# DM0255_MTP006.net
KiCad netlist of a schematic drawn in Altium Designer
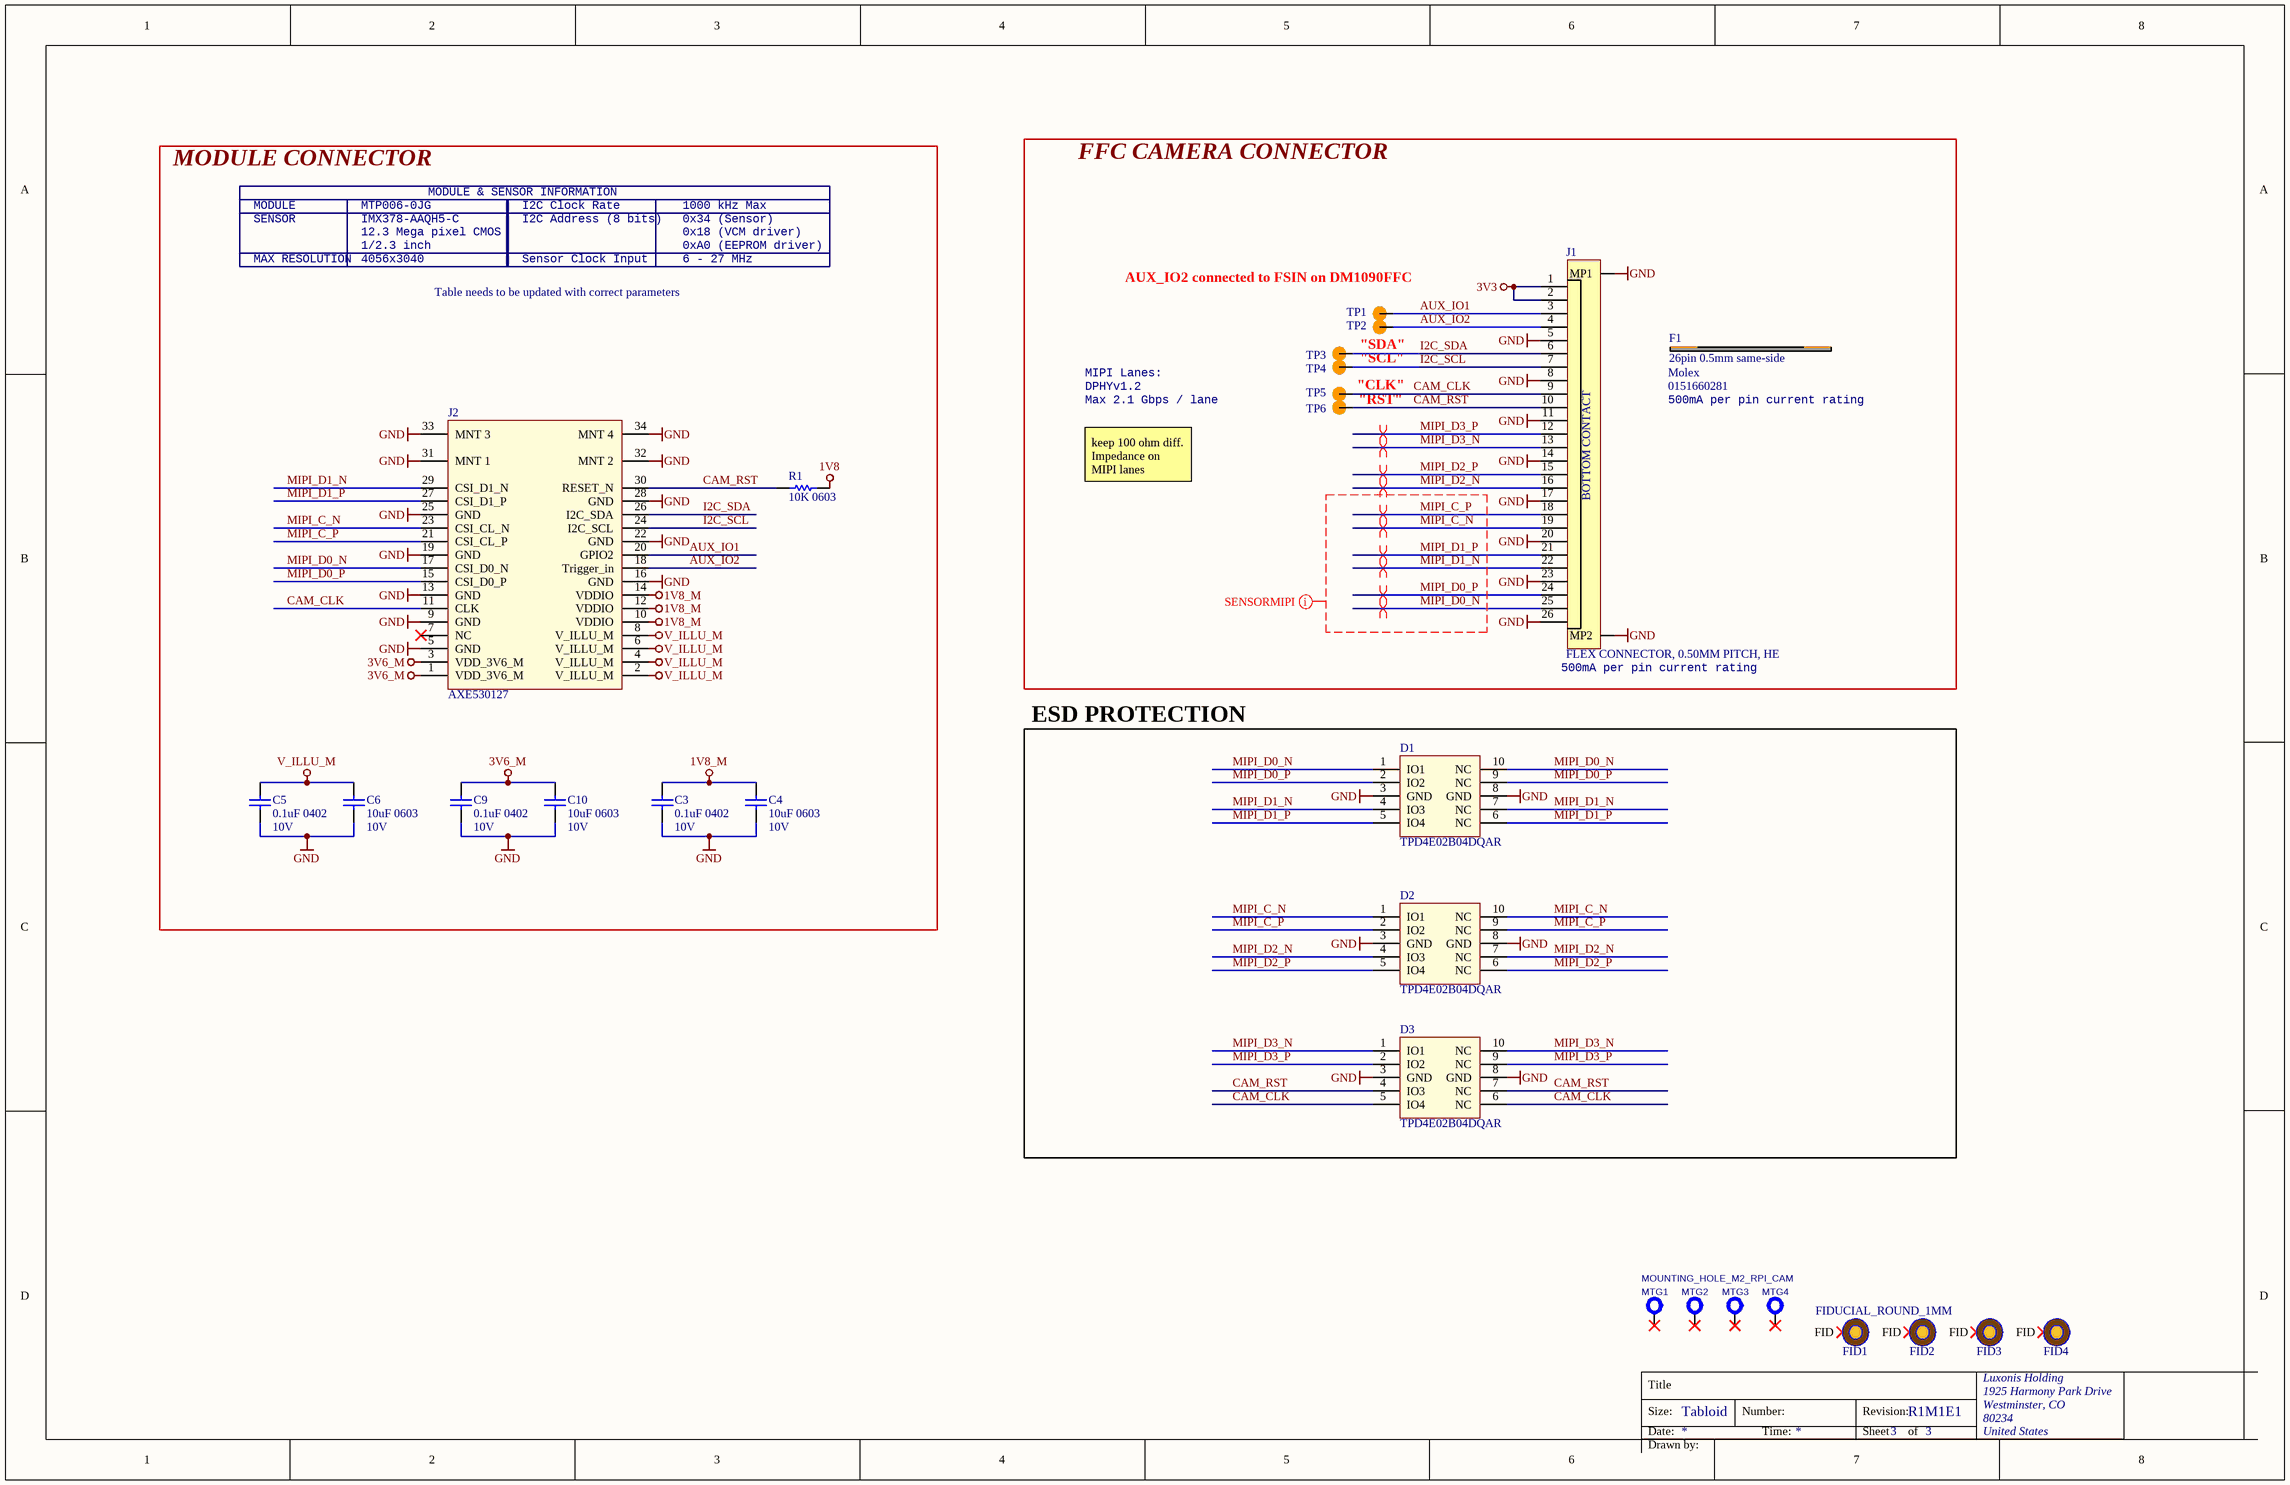
[diagram p0: DM0255_MTP006.SchDoc]

(export (version "E")
  (design (tool "Eeschema 10.0.6"))
  (components
    (comp (ref "C3")
      (value "0.1uF 0402")
      (footprint "CAP_Altium_Vault_Generic:CAPC0402(1005)70_N")
      (description "CAP CER 0.1UF 10V X7R 0402 5%")
      (fields (field (name "TOLERANCE") "5%") (field (name "VOLTAGE RATING") "10V"))
      (libsource (lib "LuxonisMaster") (part "GRM155R71A104JA01D"))
    )
    (comp (ref "C4")
      (value "10uF 0603")
      (footprint "CAP_Altium_Vault_Generic:CAPC0603(1608)100_N")
      (description "CAP CER 10UF 10V X5R 0603 20%")
      (fields (field (name "TOLERANCE") "20%") (field (name "VOLTAGE RATING") "10V"))
      (libsource (lib "LuxonisMaster") (part "GRM188R61A106ME69D"))
    )
    (comp (ref "C5")
      (value "0.1uF 0402")
      (footprint "CAP_Altium_Vault_Generic:CAPC0402(1005)70_N")
      (description "CAP CER 0.1UF 10V X7R 0402 5%")
      (fields (field (name "TOLERANCE") "5%") (field (name "VOLTAGE RATING") "10V"))
      (libsource (lib "LuxonisMaster") (part "GRM155R71A104JA01D"))
    )
    (comp (ref "C6")
      (value "10uF 0603")
      (footprint "CAP_Altium_Vault_Generic:CAPC0603(1608)100_N")
      (description "CAP CER 10UF 10V X5R 0603 20%")
      (fields (field (name "TOLERANCE") "20%") (field (name "VOLTAGE RATING") "10V"))
      (libsource (lib "LuxonisMaster") (part "GRM188R61A106ME69D"))
    )
    (comp (ref "C9")
      (value "0.1uF 0402")
      (footprint "CAP_Altium_Vault_Generic:CAPC0402(1005)70_N")
      (description "CAP CER 0.1UF 10V X7R 0402 5%")
      (fields (field (name "TOLERANCE") "5%") (field (name "VOLTAGE RATING") "10V"))
      (libsource (lib "LuxonisMaster") (part "GRM155R71A104JA01D"))
    )
    (comp (ref "C10")
      (value "10uF 0603")
      (footprint "CAP_Altium_Vault_Generic:CAPC0603(1608)100_N")
      (description "CAP CER 10UF 10V X5R 0603 20%")
      (fields (field (name "TOLERANCE") "20%") (field (name "VOLTAGE RATING") "10V"))
      (libsource (lib "LuxonisMaster") (part "GRM188R61A106ME69D"))
    )
    (comp (ref "D1")
      (value "TPD4E02B04DQAR")
      (footprint "LuxonisMaster:TPD4E02B04DQAR")
      (libsource (lib "LuxonisMaster") (part "TPD4E02B04DQAR"))
    )
    (comp (ref "D2")
      (value "TPD4E02B04DQAR")
      (footprint "LuxonisMaster:TPD4E02B04DQAR")
      (libsource (lib "LuxonisMaster") (part "TPD4E02B04DQAR"))
    )
    (comp (ref "D3")
      (value "TPD4E02B04DQAR")
      (footprint "LuxonisMaster:TPD4E02B04DQAR")
      (libsource (lib "LuxonisMaster") (part "TPD4E02B04DQAR"))
    )
    (comp (ref "F1")
      (value "26pin 0.5mm same-side")
      (description "CABLE FFC 26POS 0.50MM 6\"")
      (fields
        (field (name "MANUFACTURER 1") "Molex")
        (field (name "MANUFACTURER PART NUMBER 1") "0151660281")
      )
      (libsource (lib "BG0249_R1M1E1") (part "0151660281"))
    )
    (comp (ref "FID1")
      (value "FIDUCIAL_ROUND_1MM")
      (footprint "LuxonisMaster:FIDUCIAL_ROUND_1MM")
      (description "Fiducial with various available footprints")
      (libsource (lib "LuxonisMaster") (part "FIDUCIAL"))
    )
    (comp (ref "FID2")
      (value "FIDUCIAL_ROUND_1MM")
      (footprint "LuxonisMaster:FIDUCIAL_ROUND_1MM")
      (description "Fiducial with various available footprints")
      (libsource (lib "LuxonisMaster") (part "FIDUCIAL"))
    )
    (comp (ref "FID3")
      (value "FIDUCIAL_ROUND_1MM")
      (footprint "LuxonisMaster:FIDUCIAL_ROUND_1MM")
      (description "Fiducial with various available footprints")
      (libsource (lib "LuxonisMaster") (part "FIDUCIAL"))
    )
    (comp (ref "FID4")
      (value "FIDUCIAL_ROUND_1MM")
      (footprint "LuxonisMaster:FIDUCIAL_ROUND_1MM")
      (description "Fiducial with various available footprints")
      (libsource (lib "LuxonisMaster") (part "FIDUCIAL"))
    )
    (comp (ref "J1")
      (value "FLEX CONNECTOR, 0.50MM PITCH, HE")
      (footprint "F32R-1A7H1-11026")
      (description "26 Position FFC, FPC Connector Contacts, Bottom 0.020\" (0.50mm) Surface Mount, Right Angle")
      (libsource (lib "DM0255") (part "F32R-1A7H1-11026"))
    )
    (comp (ref "J2")
      (value "AXE530127")
      (footprint "AXE530127")
      (description "Narrow Pitch Connector (Board to FPC) 0.4mm")
      (libsource (lib "DM0255") (part "AXE530127"))
    )
    (comp (ref "MTG1")
      (value "MOUNTING_HOLE_M2_RPI_CAM")
      (footprint "LuxonisMaster:MOUNTING_HOLE_M2_RPI_CAM")
      (description "=CurrentFootprint")
      (libsource (lib "LuxonisMaster") (part "MP_Mounting-Holes"))
    )
    (comp (ref "MTG2")
      (value "MOUNTING_HOLE_M2_RPI_CAM")
      (footprint "LuxonisMaster:MOUNTING_HOLE_M2_RPI_CAM")
      (description "=CurrentFootprint")
      (libsource (lib "LuxonisMaster") (part "MP_Mounting-Holes"))
    )
    (comp (ref "MTG3")
      (value "MOUNTING_HOLE_M2_RPI_CAM")
      (footprint "LuxonisMaster:MOUNTING_HOLE_M2_RPI_CAM")
      (description "=CurrentFootprint")
      (libsource (lib "LuxonisMaster") (part "MP_Mounting-Holes"))
    )
    (comp (ref "MTG4")
      (value "MOUNTING_HOLE_M2_RPI_CAM")
      (footprint "LuxonisMaster:MOUNTING_HOLE_M2_RPI_CAM")
      (description "=CurrentFootprint")
      (libsource (lib "LuxonisMaster") (part "MP_Mounting-Holes"))
    )
    (comp (ref "R1")
      (value "10K 0603")
      (footprint "RES_Altium_Vault_Generic:RESC0603(1608)_N")
      (description "RES SMD 10K OHM 1% 1/10W 0603")
      (fields (field (name "TOLERANCE") "1%"))
      (libsource (lib "LuxonisMaster") (part "RC0603FR-0710KL"))
    )
    (comp (ref "TP1")
      (value "TP100_200_NS")
      (footprint "LuxonisMaster:TP100_200_NS")
      (libsource (lib "LuxonisMaster") (part "TEST_POINT"))
    )
    (comp (ref "TP2")
      (value "TP100_200_NS")
      (footprint "LuxonisMaster:TP100_200_NS")
      (libsource (lib "LuxonisMaster") (part "TEST_POINT"))
    )
    (comp (ref "TP3")
      (value "TP100_200_NS")
      (footprint "LuxonisMaster:TP100_200_NS")
      (libsource (lib "LuxonisMaster") (part "TEST_POINT"))
    )
    (comp (ref "TP4")
      (value "TP100_200_NS")
      (footprint "LuxonisMaster:TP100_200_NS")
      (libsource (lib "LuxonisMaster") (part "TEST_POINT"))
    )
    (comp (ref "TP5")
      (value "TP100_200_NS")
      (footprint "LuxonisMaster:TP100_200_NS")
      (libsource (lib "LuxonisMaster") (part "TEST_POINT"))
    )
    (comp (ref "TP6")
      (value "TP100_200_NS")
      (footprint "LuxonisMaster:TP100_200_NS")
      (libsource (lib "LuxonisMaster") (part "TEST_POINT"))
    )
  )
  (nets
    (net (code "1") (name "/AUX_IO1") (class "Default")
      (node (ref "J1") (pin "3") (pinfunction "3_3") (pintype "passive"))
      (node (ref "J2") (pin "20") (pinfunction "GPIO2_20") (pintype "passive"))
      (node (ref "TP1") (pin "1") (pintype "passive"))
    )
    (net (code "2") (name "/AUX_IO2") (class "Default")
      (node (ref "J1") (pin "4") (pinfunction "4_4") (pintype "passive"))
      (node (ref "J2") (pin "18") (pinfunction "Trigger_in_18") (pintype "passive"))
      (node (ref "TP2") (pin "1") (pintype "passive"))
    )
    (net (code "3") (name "/CAM_CLK") (class "Default")
      (node (ref "D3") (pin "5") (pinfunction "IO4_5") (pintype "passive"))
      (node (ref "D3") (pin "6") (pinfunction "NC_6") (pintype "passive"))
      (node (ref "J1") (pin "9") (pinfunction "9_9") (pintype "passive"))
      (node (ref "J2") (pin "11") (pinfunction "CLK_11") (pintype "passive"))
      (node (ref "TP5") (pin "1") (pintype "passive"))
    )
    (net (code "4") (name "/CAM_RST") (class "Default")
      (node (ref "D3") (pin "4") (pinfunction "IO3_4") (pintype "passive"))
      (node (ref "D3") (pin "7") (pinfunction "NC_7") (pintype "passive"))
      (node (ref "J1") (pin "10") (pinfunction "10_10") (pintype "passive"))
      (node (ref "J2") (pin "30") (pinfunction "RESET_N_30") (pintype "passive"))
      (node (ref "R1") (pin "1") (pinfunction "1_1") (pintype "passive"))
      (node (ref "TP6") (pin "1") (pintype "passive"))
    )
    (net (code "5") (name "/I2C_SCL") (class "Default")
      (node (ref "J1") (pin "7") (pinfunction "7_7") (pintype "passive"))
      (node (ref "J2") (pin "24") (pinfunction "I2C_SCL_24") (pintype "passive"))
      (node (ref "TP4") (pin "1") (pintype "passive"))
    )
    (net (code "6") (name "/I2C_SDA") (class "Default")
      (node (ref "J1") (pin "6") (pinfunction "6_6") (pintype "passive"))
      (node (ref "J2") (pin "26") (pinfunction "I2C_SDA_26") (pintype "passive"))
      (node (ref "TP3") (pin "1") (pintype "passive"))
    )
    (net (code "7") (name "/MIPI_C_N") (class "Default")
      (node (ref "D2") (pin "1") (pinfunction "IO1_1") (pintype "passive"))
      (node (ref "D2") (pin "10") (pinfunction "NC_10") (pintype "passive"))
      (node (ref "J1") (pin "19") (pinfunction "19_19") (pintype "passive"))
      (node (ref "J2") (pin "23") (pinfunction "CSI_CL_N_23") (pintype "passive"))
    )
    (net (code "8") (name "/MIPI_C_P") (class "Default")
      (node (ref "D2") (pin "2") (pinfunction "IO2_2") (pintype "passive"))
      (node (ref "D2") (pin "9") (pinfunction "NC_9") (pintype "passive"))
      (node (ref "J1") (pin "18") (pinfunction "18_18") (pintype "passive"))
      (node (ref "J2") (pin "21") (pinfunction "CSI_CL_P_21") (pintype "passive"))
    )
    (net (code "9") (name "/MIPI_D0_N") (class "Default")
      (node (ref "D1") (pin "1") (pinfunction "IO1_1") (pintype "passive"))
      (node (ref "D1") (pin "10") (pinfunction "NC_10") (pintype "passive"))
      (node (ref "J1") (pin "25") (pinfunction "25_25") (pintype "passive"))
      (node (ref "J2") (pin "17") (pinfunction "CSI_D0_N_17") (pintype "passive"))
    )
    (net (code "10") (name "/MIPI_D0_P") (class "Default")
      (node (ref "D1") (pin "2") (pinfunction "IO2_2") (pintype "passive"))
      (node (ref "D1") (pin "9") (pinfunction "NC_9") (pintype "passive"))
      (node (ref "J1") (pin "24") (pinfunction "24_24") (pintype "passive"))
      (node (ref "J2") (pin "15") (pinfunction "CSI_D0_P_15") (pintype "passive"))
    )
    (net (code "11") (name "/MIPI_D1_N") (class "Default")
      (node (ref "D1") (pin "4") (pinfunction "IO3_4") (pintype "passive"))
      (node (ref "D1") (pin "7") (pinfunction "NC_7") (pintype "passive"))
      (node (ref "J1") (pin "22") (pinfunction "22_22") (pintype "passive"))
      (node (ref "J2") (pin "29") (pinfunction "CSI_D1_N_29") (pintype "passive"))
    )
    (net (code "12") (name "/MIPI_D1_P") (class "Default")
      (node (ref "D1") (pin "5") (pinfunction "IO4_5") (pintype "passive"))
      (node (ref "D1") (pin "6") (pinfunction "NC_6") (pintype "passive"))
      (node (ref "J1") (pin "21") (pinfunction "21_21") (pintype "passive"))
      (node (ref "J2") (pin "27") (pinfunction "CSI_D1_P_27") (pintype "passive"))
    )
    (net (code "13") (name "/MIPI_D2_N") (class "Default")
      (node (ref "D2") (pin "4") (pinfunction "IO3_4") (pintype "passive"))
      (node (ref "D2") (pin "7") (pinfunction "NC_7") (pintype "passive"))
      (node (ref "J1") (pin "16") (pinfunction "16_16") (pintype "passive"))
    )
    (net (code "14") (name "/MIPI_D2_P") (class "Default")
      (node (ref "D2") (pin "5") (pinfunction "IO4_5") (pintype "passive"))
      (node (ref "D2") (pin "6") (pinfunction "NC_6") (pintype "passive"))
      (node (ref "J1") (pin "15") (pinfunction "15_15") (pintype "passive"))
    )
    (net (code "15") (name "/MIPI_D3_N") (class "Default")
      (node (ref "D3") (pin "1") (pinfunction "IO1_1") (pintype "passive"))
      (node (ref "D3") (pin "10") (pinfunction "NC_10") (pintype "passive"))
      (node (ref "J1") (pin "13") (pinfunction "13_13") (pintype "passive"))
    )
    (net (code "16") (name "/MIPI_D3_P") (class "Default")
      (node (ref "D3") (pin "2") (pinfunction "IO2_2") (pintype "passive"))
      (node (ref "D3") (pin "9") (pinfunction "NC_9") (pintype "passive"))
      (node (ref "J1") (pin "12") (pinfunction "12_12") (pintype "passive"))
    )
    (net (code "17") (name "1V8") (class "Default")
      (node (ref "R1") (pin "2") (pinfunction "2_2") (pintype "passive"))
    )
    (net (code "18") (name "1V8_M") (class "Default")
      (node (ref "C3") (pin "2") (pinfunction "2_2") (pintype "passive"))
      (node (ref "C4") (pin "2") (pinfunction "2_2") (pintype "passive"))
      (node (ref "J2") (pin "10") (pinfunction "VDDIO_10") (pintype "passive"))
      (node (ref "J2") (pin "12") (pinfunction "VDDIO_12") (pintype "passive"))
      (node (ref "J2") (pin "14") (pinfunction "VDDIO_14") (pintype "passive"))
    )
    (net (code "19") (name "3V3") (class "Default")
      (node (ref "J1") (pin "1") (pinfunction "1_1") (pintype "passive"))
      (node (ref "J1") (pin "2") (pinfunction "2_2") (pintype "passive"))
    )
    (net (code "20") (name "3V6_M") (class "Default")
      (node (ref "C10") (pin "2") (pinfunction "2_2") (pintype "passive"))
      (node (ref "C9") (pin "2") (pinfunction "2_2") (pintype "passive"))
      (node (ref "J2") (pin "1") (pinfunction "VDD_3V6_M_1") (pintype "passive"))
      (node (ref "J2") (pin "3") (pinfunction "VDD_3V6_M_3") (pintype "passive"))
    )
    (net (code "21") (name "GND") (class "Default")
      (node (ref "C10") (pin "1") (pinfunction "1_1") (pintype "passive"))
      (node (ref "C3") (pin "1") (pinfunction "1_1") (pintype "passive"))
      (node (ref "C4") (pin "1") (pinfunction "1_1") (pintype "passive"))
      (node (ref "C5") (pin "1") (pinfunction "1_1") (pintype "passive"))
      (node (ref "C6") (pin "1") (pinfunction "1_1") (pintype "passive"))
      (node (ref "C9") (pin "1") (pinfunction "1_1") (pintype "passive"))
      (node (ref "D1") (pin "3") (pinfunction "GND_3") (pintype "passive"))
      (node (ref "D1") (pin "8") (pinfunction "GND_8") (pintype "passive"))
      (node (ref "D2") (pin "3") (pinfunction "GND_3") (pintype "passive"))
      (node (ref "D2") (pin "8") (pinfunction "GND_8") (pintype "passive"))
      (node (ref "D3") (pin "3") (pinfunction "GND_3") (pintype "passive"))
      (node (ref "D3") (pin "8") (pinfunction "GND_8") (pintype "passive"))
      (node (ref "J1") (pin "11") (pinfunction "11_11") (pintype "passive"))
      (node (ref "J1") (pin "14") (pinfunction "14_14") (pintype "passive"))
      (node (ref "J1") (pin "17") (pinfunction "17_17") (pintype "passive"))
      (node (ref "J1") (pin "20") (pinfunction "20_20") (pintype "passive"))
      (node (ref "J1") (pin "23") (pinfunction "23_23") (pintype "passive"))
      (node (ref "J1") (pin "26") (pinfunction "26_26") (pintype "passive"))
      (node (ref "J1") (pin "5") (pinfunction "5_5") (pintype "passive"))
      (node (ref "J1") (pin "8") (pinfunction "8_8") (pintype "passive"))
      (node (ref "J1") (pin "MP1") (pinfunction "MP1_MP1") (pintype "passive"))
      (node (ref "J1") (pin "MP2") (pinfunction "MP2_MP2") (pintype "passive"))
      (node (ref "J2") (pin "13") (pinfunction "GND_13") (pintype "passive"))
      (node (ref "J2") (pin "16") (pinfunction "GND_16") (pintype "passive"))
      (node (ref "J2") (pin "19") (pinfunction "GND_19") (pintype "passive"))
      (node (ref "J2") (pin "22") (pinfunction "GND_22") (pintype "passive"))
      (node (ref "J2") (pin "25") (pinfunction "GND_25") (pintype "passive"))
      (node (ref "J2") (pin "28") (pinfunction "GND_28") (pintype "passive"))
      (node (ref "J2") (pin "31") (pinfunction "MNT_1_31") (pintype "passive"))
      (node (ref "J2") (pin "32") (pinfunction "MNT_2_32") (pintype "passive"))
      (node (ref "J2") (pin "33") (pinfunction "MNT_3_33") (pintype "passive"))
      (node (ref "J2") (pin "34") (pinfunction "MNT_4_34") (pintype "passive"))
      (node (ref "J2") (pin "5") (pinfunction "GND_5") (pintype "passive"))
      (node (ref "J2") (pin "9") (pinfunction "GND_9") (pintype "passive"))
    )
    (net (code "22") (name "V_ILLU_M") (class "Default")
      (node (ref "C5") (pin "2") (pinfunction "2_2") (pintype "passive"))
      (node (ref "C6") (pin "2") (pinfunction "2_2") (pintype "passive"))
      (node (ref "J2") (pin "2") (pinfunction "V_ILLU_M_2") (pintype "passive"))
      (node (ref "J2") (pin "4") (pinfunction "V_ILLU_M_4") (pintype "passive"))
      (node (ref "J2") (pin "6") (pinfunction "V_ILLU_M_6") (pintype "passive"))
      (node (ref "J2") (pin "8") (pinfunction "V_ILLU_M_8") (pintype "passive"))
    )
    (net (code "23") (name "unconnected-(FID1-PadFID)") (class "Default")
      (node (ref "FID1") (pin "FID") (pinfunction "FID_FID") (pintype "input+no_connect"))
    )
    (net (code "24") (name "unconnected-(FID2-PadFID)") (class "Default")
      (node (ref "FID2") (pin "FID") (pinfunction "FID_FID") (pintype "input+no_connect"))
    )
    (net (code "25") (name "unconnected-(FID3-PadFID)") (class "Default")
      (node (ref "FID3") (pin "FID") (pinfunction "FID_FID") (pintype "input+no_connect"))
    )
    (net (code "26") (name "unconnected-(FID4-PadFID)") (class "Default")
      (node (ref "FID4") (pin "FID") (pinfunction "FID_FID") (pintype "input+no_connect"))
    )
    (net (code "27") (name "unconnected-(J2-NC-Pad7)") (class "Default")
      (node (ref "J2") (pin "7") (pinfunction "NC_7") (pintype "passive+no_connect"))
    )
    (net (code "28") (name "unconnected-(MTG1-Pad1)") (class "Default")
      (node (ref "MTG1") (pin "1") (pintype "passive+no_connect"))
    )
    (net (code "29") (name "unconnected-(MTG2-Pad1)") (class "Default")
      (node (ref "MTG2") (pin "1") (pintype "passive+no_connect"))
    )
    (net (code "30") (name "unconnected-(MTG3-Pad1)") (class "Default")
      (node (ref "MTG3") (pin "1") (pintype "passive+no_connect"))
    )
    (net (code "31") (name "unconnected-(MTG4-Pad1)") (class "Default")
      (node (ref "MTG4") (pin "1") (pintype "passive+no_connect"))
    )
  )
)
